# MOTORES.net
KiCad netlist of a schematic drawn in Altium Designer
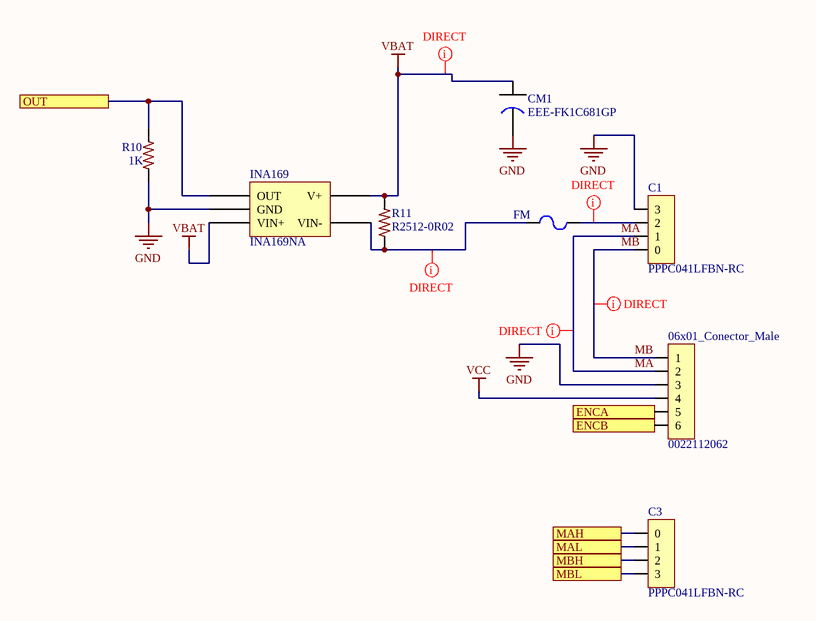
[diagram p0: MOTORES.SchDoc]

(export (version "E")
  (design (tool "Eeschema 10.0.6"))
  (components
    (comp (ref "06x01_Conector_Male")
      (value "0022112062")
      (footprint "06x01_Conector_Male")
      (description "CONN HEADER 6POS .100 VERT GOLD")
      (libsource (lib "Schlib1") (part "06x01_Conector_Male"))
    )
    (comp (ref "C1")
      (value "PPPC041LFBN-RC")
      (footprint "04x01_Conector_Female")
      (description "4 Position Header Connector 0.100\" (2.54mm) Through Hole Gold")
      (libsource (lib "Schlib1") (part "04x01_Conector_Female-SCH"))
    )
    (comp (ref "C3")
      (value "PPPC041LFBN-RC")
      (footprint "04x01_Conector_Female")
      (description "4 Position Header Connector 0.100\" (2.54mm) Through Hole Gold")
      (libsource (lib "") (part "04x01_Conector_Female-SCH_1"))
    )
    (comp (ref "CM1")
      (value "EEE-FK1C681GP")
      (footprint "EEE-FK1C681GP")
      (description "Aluminum Electrolytic Capacitors - SMD Al Lytic Cap SMT FK Series 105C")
      (libsource (lib "Schlib1") (part "CAP AL 680UF/16V"))
    )
    (comp (ref "FM")
      (value "MF-MSMF250/16X")
      (footprint "RESC4632X16N")
      (description "PTC RESETTABLE .30A 30V 1812")
      (libsource (lib "IMBEL") (part "MF-MSMF250/16X-01.A.1"))
    )
    (comp (ref "INA169")
      (value "INA169NA")
      (footprint "SOT95P280X125-5N")
      (description "IC CURRENT MONITOR 0.5% SOT23-5")
      (libsource (lib "IMBEL") (part "ina169"))
    )
    (comp (ref "R10")
      (value "1K")
      (footprint "0402-RES-HD")
      (description "RES 1K OHM 1/10W 1% 0402 SMD")
      (fields (field (name "PART NO") "ERJ-2RKF1001X"))
      (libsource (lib "IMBEL") (part "RESISTOR"))
    )
    (comp (ref "R11")
      (value "R2512-0R02")
      (footprint "2512-RES-HD")
      (description "RES .02 OHM 2W 1% 2512 SMD")
      (fields (field (name "PART NO") "WSL2512R0200FEA18"))
      (libsource (lib "IMBEL") (part "R2512-0R02-4"))
    )
  )
  (nets
    (net (code "1") (name "/ENCA") (class "Default")
      (node (ref "06x01_Conector_Male") (pin "5") (pinfunction "5_5") (pintype "passive"))
    )
    (net (code "2") (name "/ENCB") (class "Default")
      (node (ref "06x01_Conector_Male") (pin "6") (pinfunction "6_6") (pintype "passive"))
    )
    (net (code "3") (name "/MA") (class "Default")
      (node (ref "06x01_Conector_Male") (pin "2") (pinfunction "2_2") (pintype "passive"))
      (node (ref "C1") (pin "1") (pinfunction "1_1") (pintype "passive"))
    )
    (net (code "4") (name "/MAH") (class "Default")
      (node (ref "C3") (pin "0") (pinfunction "0_0") (pintype "passive"))
    )
    (net (code "5") (name "/MAL") (class "Default")
      (node (ref "C3") (pin "1") (pinfunction "1_1") (pintype "passive"))
    )
    (net (code "6") (name "/MB") (class "Default")
      (node (ref "06x01_Conector_Male") (pin "1") (pinfunction "1_1") (pintype "passive"))
      (node (ref "C1") (pin "0") (pinfunction "0_0") (pintype "passive"))
    )
    (net (code "7") (name "/MBH") (class "Default")
      (node (ref "C3") (pin "2") (pinfunction "2_2") (pintype "passive"))
    )
    (net (code "8") (name "/MBL") (class "Default")
      (node (ref "C3") (pin "3") (pinfunction "3_3") (pintype "passive"))
    )
    (net (code "9") (name "/OUT") (class "Default")
      (node (ref "INA169") (pin "1") (pinfunction "OUT_1") (pintype "passive"))
      (node (ref "R10") (pin "2") (pinfunction "2_2") (pintype "passive"))
    )
    (net (code "10") (name "GND") (class "Default")
      (node (ref "06x01_Conector_Male") (pin "3") (pinfunction "3_3") (pintype "passive"))
      (node (ref "C1") (pin "3") (pinfunction "3_3") (pintype "passive"))
      (node (ref "CM1") (pin "2") (pinfunction "2_2") (pintype "passive"))
      (node (ref "INA169") (pin "2") (pinfunction "GND_2") (pintype "passive"))
      (node (ref "R10") (pin "1") (pinfunction "1_1") (pintype "passive"))
    )
    (net (code "11") (name "Net-(C1-Pad2)") (class "Default")
      (node (ref "C1") (pin "2") (pinfunction "2_2") (pintype "passive"))
      (node (ref "FM") (pin "1") (pinfunction "1_1") (pintype "passive"))
    )
    (net (code "12") (name "Net-(INA169-VIN-)") (class "Default")
      (node (ref "FM") (pin "2") (pinfunction "2_2") (pintype "passive"))
      (node (ref "INA169") (pin "5") (pinfunction "VIN-_5") (pintype "passive"))
      (node (ref "R11") (pin "1") (pinfunction "1_1") (pintype "passive"))
    )
    (net (code "13") (name "VBAT") (class "Default")
      (node (ref "CM1") (pin "1") (pinfunction "1_1") (pintype "passive"))
      (node (ref "INA169") (pin "3") (pinfunction "VIN+_3") (pintype "passive"))
      (node (ref "INA169") (pin "4") (pinfunction "V+_4") (pintype "passive"))
      (node (ref "R11") (pin "2") (pinfunction "2_2") (pintype "passive"))
    )
    (net (code "14") (name "VCC") (class "Default")
      (node (ref "06x01_Conector_Male") (pin "4") (pinfunction "4_4") (pintype "passive"))
    )
  )
)
